# input_amp.net
KiCad netlist of a schematic drawn in EAGLE
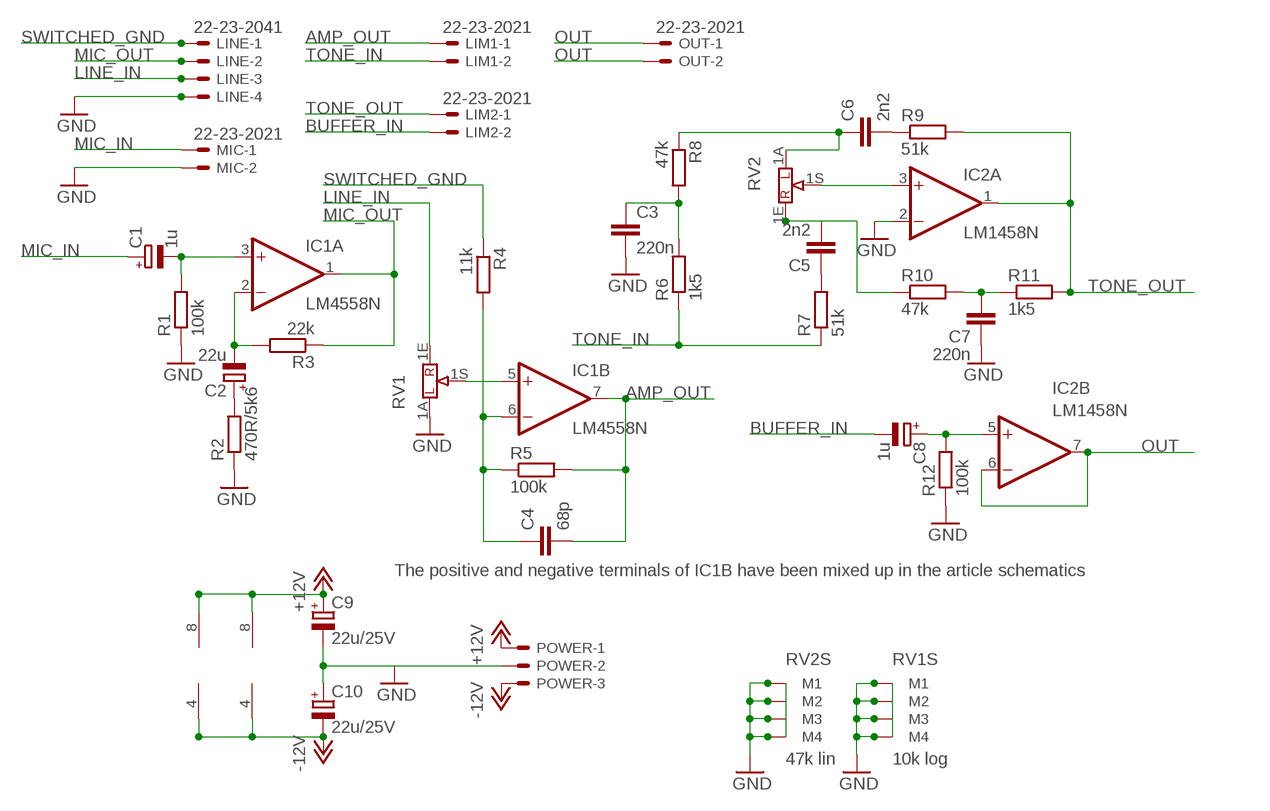
[diagram p0: schematic, sheet 1]

(export (version "E")
  (design (tool "Eeschema 10.0.6"))
  (components
    (comp (ref "C1")
      (value "1u")
      (footprint "eagle-import:E2,5-5")
      (libsource (lib "eagle-import") (part "CPOL-EUE2.5-5"))
    )
    (comp (ref "C2")
      (value "22u")
      (footprint "eagle-import:E2,5-5")
      (libsource (lib "eagle-import") (part "CPOL-EUE2.5-5"))
    )
    (comp (ref "C3")
      (value "220n")
      (footprint "eagle-import:C050-025X075")
      (libsource (lib "eagle-import") (part "C-EU050-025X075"))
    )
    (comp (ref "C4")
      (value "68p")
      (footprint "eagle-import:C025-025X050")
      (libsource (lib "eagle-import") (part "C-EU025-025X050"))
    )
    (comp (ref "C5")
      (value "2n2")
      (footprint "eagle-import:C050-025X075")
      (libsource (lib "eagle-import") (part "C-EU050-025X075"))
    )
    (comp (ref "C6")
      (value "2n2")
      (footprint "eagle-import:C050-025X075")
      (libsource (lib "eagle-import") (part "C-EU050-025X075"))
    )
    (comp (ref "C7")
      (value "220n")
      (footprint "eagle-import:C050-025X075")
      (libsource (lib "eagle-import") (part "C-EU050-025X075"))
    )
    (comp (ref "C8")
      (value "1u")
      (footprint "eagle-import:E2,5-5")
      (libsource (lib "eagle-import") (part "CPOL-EUE2.5-5"))
    )
    (comp (ref "C9")
      (value "22u/25V")
      (footprint "eagle-import:E2,5-5")
      (libsource (lib "eagle-import") (part "CPOL-EUE2.5-5"))
    )
    (comp (ref "C10")
      (value "22u/25V")
      (footprint "eagle-import:E2,5-5")
      (libsource (lib "eagle-import") (part "CPOL-EUE2.5-5"))
    )
    (comp (ref "IC1")
      (value "LM4558N")
      (footprint "eagle-import:DIL08")
      (libsource (lib "eagle-import") (part "4558NLM"))
    )
    (comp (ref "IC2")
      (value "LM1458N")
      (footprint "eagle-import:DIL08")
      (libsource (lib "eagle-import") (part "1458NLM"))
    )
    (comp (ref "LIM1")
      (value "22-23-2021")
      (footprint "eagle-import:22-23-2021")
      (fields (field (name "MF") "MOLEX"))
      (libsource (lib "eagle-import") (part "22-23-2021"))
    )
    (comp (ref "LIM2")
      (value "22-23-2021")
      (footprint "eagle-import:22-23-2021")
      (fields (field (name "MF") "MOLEX"))
      (libsource (lib "eagle-import") (part "22-23-2021"))
    )
    (comp (ref "LINE")
      (value "22-23-2041")
      (footprint "eagle-import:22-23-2041")
      (fields (field (name "MF") "MOLEX"))
      (libsource (lib "eagle-import") (part "22-23-2041"))
    )
    (comp (ref "MIC")
      (value "22-23-2021")
      (footprint "eagle-import:22-23-2021")
      (fields (field (name "MF") "MOLEX"))
      (libsource (lib "eagle-import") (part "22-23-2021"))
    )
    (comp (ref "OUT")
      (value "22-23-2021")
      (footprint "eagle-import:22-23-2021")
      (fields (field (name "MF") "MOLEX"))
      (libsource (lib "eagle-import") (part "22-23-2021"))
    )
    (comp (ref "POWER")
      (value "KK-156-3")
      (footprint "eagle-import:KK-156-3")
      (libsource (lib "eagle-import") (part "KK-156-3"))
    )
    (comp (ref "R1")
      (value "100k")
      (footprint "eagle-import:0207_7")
      (libsource (lib "eagle-import") (part "R-EU_0207/7"))
    )
    (comp (ref "R2")
      (value "470R/5k6")
      (footprint "eagle-import:0207_7")
      (libsource (lib "eagle-import") (part "R-EU_0207/7"))
    )
    (comp (ref "R3")
      (value "22k")
      (footprint "eagle-import:0207_7")
      (libsource (lib "eagle-import") (part "R-EU_0207/7"))
    )
    (comp (ref "R4")
      (value "11k")
      (footprint "eagle-import:0207_7")
      (libsource (lib "eagle-import") (part "R-EU_0207/7"))
    )
    (comp (ref "R5")
      (value "100k")
      (footprint "eagle-import:0207_7")
      (libsource (lib "eagle-import") (part "R-EU_0207/7"))
    )
    (comp (ref "R6")
      (value "1k5")
      (footprint "eagle-import:0207_7")
      (libsource (lib "eagle-import") (part "R-EU_0207/7"))
    )
    (comp (ref "R7")
      (value "51k")
      (footprint "eagle-import:0207_7")
      (libsource (lib "eagle-import") (part "R-EU_0207/7"))
    )
    (comp (ref "R8")
      (value "47k")
      (footprint "eagle-import:0207_7")
      (libsource (lib "eagle-import") (part "R-EU_0207/7"))
    )
    (comp (ref "R9")
      (value "51k")
      (footprint "eagle-import:0207_7")
      (libsource (lib "eagle-import") (part "R-EU_0207/7"))
    )
    (comp (ref "R10")
      (value "47k")
      (footprint "eagle-import:0207_7")
      (libsource (lib "eagle-import") (part "R-EU_0207/7"))
    )
    (comp (ref "R11")
      (value "1k5")
      (footprint "eagle-import:0207_7")
      (libsource (lib "eagle-import") (part "R-EU_0207/7"))
    )
    (comp (ref "R12")
      (value "100k")
      (footprint "eagle-import:0207_7")
      (libsource (lib "eagle-import") (part "R-EU_0207/7"))
    )
    (comp (ref "RV1")
      (value "10k log")
      (footprint "eagle-import:POT16_W_BRACKET")
      (libsource (lib "eagle-import") (part "POT16_W_BRACKET{dblquote}{dblquote}"))
    )
    (comp (ref "RV2")
      (value "47k lin")
      (footprint "eagle-import:POT16_W_BRACKET")
      (libsource (lib "eagle-import") (part "POT16_W_BRACKET{dblquote}{dblquote}"))
    )
  )
  (nets
    (net (code "1") (name "+12V") (class "Default")
      (node (ref "C9") (pin "+") (pinfunction "+_+") (pintype "passive"))
      (node (ref "IC1") (pin "8") (pinfunction "V+_8") (pintype "power_in"))
      (node (ref "IC2") (pin "8") (pinfunction "V+_8") (pintype "power_in"))
      (node (ref "POWER") (pin "1") (pinfunction "S_1") (pintype "passive"))
    )
    (net (code "2") (name "-12V") (class "Default")
      (node (ref "C10") (pin "-") (pinfunction "-_-") (pintype "passive"))
      (node (ref "IC1") (pin "4") (pinfunction "V-_4") (pintype "power_in"))
      (node (ref "IC2") (pin "4") (pinfunction "V-_4") (pintype "power_in"))
      (node (ref "POWER") (pin "3") (pinfunction "S_3") (pintype "passive"))
    )
    (net (code "3") (name "/AMP_OUT") (class "Default")
      (node (ref "C4") (pin "2") (pinfunction "2_2") (pintype "passive"))
      (node (ref "IC1") (pin "7") (pinfunction "OUT_7") (pintype "output"))
      (node (ref "LIM1") (pin "1") (pinfunction "S_1") (pintype "passive"))
      (node (ref "R5") (pin "2") (pinfunction "2_2") (pintype "passive"))
    )
    (net (code "4") (name "/BUFFER_IN") (class "Default")
      (node (ref "C8") (pin "-") (pinfunction "-_-") (pintype "passive"))
      (node (ref "LIM2") (pin "2") (pinfunction "S_2") (pintype "passive"))
    )
    (net (code "5") (name "/LINE_IN") (class "Default")
      (node (ref "LINE") (pin "3") (pinfunction "S_3") (pintype "passive"))
      (node (ref "RV1") (pin "1E") (pinfunction "1E_1E") (pintype "passive"))
    )
    (net (code "6") (name "/MIC_IN") (class "Default")
      (node (ref "C1") (pin "+") (pinfunction "+_+") (pintype "passive"))
      (node (ref "MIC") (pin "1") (pinfunction "S_1") (pintype "passive"))
    )
    (net (code "7") (name "/MIC_OUT") (class "Default")
      (node (ref "IC1") (pin "1") (pinfunction "OUT_1") (pintype "output"))
      (node (ref "LINE") (pin "2") (pinfunction "S_2") (pintype "passive"))
      (node (ref "R3") (pin "1") (pinfunction "1_1") (pintype "passive"))
    )
    (net (code "8") (name "/OUT") (class "Default")
      (node (ref "IC2") (pin "6") (pinfunction "-IN_6") (pintype "input"))
      (node (ref "IC2") (pin "7") (pinfunction "OUT_7") (pintype "output"))
      (node (ref "OUT") (pin "1") (pinfunction "S_1") (pintype "passive"))
      (node (ref "OUT") (pin "2") (pinfunction "S_2") (pintype "passive"))
    )
    (net (code "9") (name "/SWITCHED_GND") (class "Default")
      (node (ref "LINE") (pin "1") (pinfunction "S_1") (pintype "passive"))
      (node (ref "R4") (pin "1") (pinfunction "1_1") (pintype "passive"))
    )
    (net (code "10") (name "/TONE_IN") (class "Default")
      (node (ref "LIM1") (pin "2") (pinfunction "S_2") (pintype "passive"))
      (node (ref "R6") (pin "1") (pinfunction "1_1") (pintype "passive"))
      (node (ref "R7") (pin "1") (pinfunction "1_1") (pintype "passive"))
    )
    (net (code "11") (name "/TONE_OUT") (class "Default")
      (node (ref "IC2") (pin "1") (pinfunction "OUT_1") (pintype "output"))
      (node (ref "LIM2") (pin "1") (pinfunction "S_1") (pintype "passive"))
      (node (ref "R11") (pin "2") (pinfunction "2_2") (pintype "passive"))
      (node (ref "R9") (pin "2") (pinfunction "2_2") (pintype "passive"))
    )
    (net (code "12") (name "GND") (class "Default")
      (node (ref "C10") (pin "+") (pinfunction "+_+") (pintype "passive"))
      (node (ref "C3") (pin "2") (pinfunction "2_2") (pintype "passive"))
      (node (ref "C7") (pin "1") (pinfunction "1_1") (pintype "passive"))
      (node (ref "C9") (pin "-") (pinfunction "-_-") (pintype "passive"))
      (node (ref "IC2") (pin "2") (pinfunction "-IN_2") (pintype "input"))
      (node (ref "LINE") (pin "4") (pinfunction "S_4") (pintype "passive"))
      (node (ref "MIC") (pin "2") (pinfunction "S_2") (pintype "passive"))
      (node (ref "POWER") (pin "2") (pinfunction "S_2") (pintype "passive"))
      (node (ref "R1") (pin "1") (pinfunction "1_1") (pintype "passive"))
      (node (ref "R12") (pin "1") (pinfunction "1_1") (pintype "passive"))
      (node (ref "R2") (pin "1") (pinfunction "1_1") (pintype "passive"))
      (node (ref "RV1") (pin "1A") (pinfunction "1A_1A") (pintype "passive"))
      (node (ref "RV1") (pin "M1") (pinfunction "M1_M1") (pintype "passive"))
      (node (ref "RV1") (pin "M2") (pinfunction "M2_M2") (pintype "passive"))
      (node (ref "RV1") (pin "M3") (pinfunction "M3_M3") (pintype "passive"))
      (node (ref "RV1") (pin "M4") (pinfunction "M4_M4") (pintype "passive"))
      (node (ref "RV2") (pin "M1") (pinfunction "M1_M1") (pintype "passive"))
      (node (ref "RV2") (pin "M2") (pinfunction "M2_M2") (pintype "passive"))
      (node (ref "RV2") (pin "M3") (pinfunction "M3_M3") (pintype "passive"))
      (node (ref "RV2") (pin "M4") (pinfunction "M4_M4") (pintype "passive"))
    )
    (net (code "13") (name "Net-(C2-Pad+)") (class "Default")
      (node (ref "C2") (pin "+") (pinfunction "+_+") (pintype "passive"))
      (node (ref "R2") (pin "2") (pinfunction "2_2") (pintype "passive"))
    )
    (net (code "14") (name "Net-(C3-Pad1)") (class "Default")
      (node (ref "C3") (pin "1") (pinfunction "1_1") (pintype "passive"))
      (node (ref "R6") (pin "2") (pinfunction "2_2") (pintype "passive"))
      (node (ref "R8") (pin "2") (pinfunction "2_2") (pintype "passive"))
    )
    (net (code "15") (name "Net-(C5-Pad1)") (class "Default")
      (node (ref "C5") (pin "1") (pinfunction "1_1") (pintype "passive"))
      (node (ref "R7") (pin "2") (pinfunction "2_2") (pintype "passive"))
    )
    (net (code "16") (name "Net-(C5-Pad2)") (class "Default")
      (node (ref "C5") (pin "2") (pinfunction "2_2") (pintype "passive"))
      (node (ref "R10") (pin "1") (pinfunction "1_1") (pintype "passive"))
      (node (ref "RV2") (pin "1E") (pinfunction "1E_1E") (pintype "passive"))
    )
    (net (code "17") (name "Net-(C6-Pad1)") (class "Default")
      (node (ref "C6") (pin "1") (pinfunction "1_1") (pintype "passive"))
      (node (ref "R8") (pin "1") (pinfunction "1_1") (pintype "passive"))
      (node (ref "RV2") (pin "1A") (pinfunction "1A_1A") (pintype "passive"))
    )
    (net (code "18") (name "Net-(C6-Pad2)") (class "Default")
      (node (ref "C6") (pin "2") (pinfunction "2_2") (pintype "passive"))
      (node (ref "R9") (pin "1") (pinfunction "1_1") (pintype "passive"))
    )
    (net (code "19") (name "Net-(C7-Pad2)") (class "Default")
      (node (ref "C7") (pin "2") (pinfunction "2_2") (pintype "passive"))
      (node (ref "R10") (pin "2") (pinfunction "2_2") (pintype "passive"))
      (node (ref "R11") (pin "1") (pinfunction "1_1") (pintype "passive"))
    )
    (net (code "20") (name "Net-(IC1A-+IN)") (class "Default")
      (node (ref "C1") (pin "-") (pinfunction "-_-") (pintype "passive"))
      (node (ref "IC1") (pin "3") (pinfunction "+IN_3") (pintype "input"))
      (node (ref "R1") (pin "2") (pinfunction "2_2") (pintype "passive"))
    )
    (net (code "21") (name "Net-(IC1A--IN)") (class "Default")
      (node (ref "C2") (pin "-") (pinfunction "-_-") (pintype "passive"))
      (node (ref "IC1") (pin "2") (pinfunction "-IN_2") (pintype "input"))
      (node (ref "R3") (pin "2") (pinfunction "2_2") (pintype "passive"))
    )
    (net (code "22") (name "Net-(IC1B-+IN)") (class "Default")
      (node (ref "IC1") (pin "5") (pinfunction "+IN_5") (pintype "input"))
      (node (ref "RV1") (pin "1S") (pinfunction "1S_1S") (pintype "passive"))
    )
    (net (code "23") (name "Net-(IC1B--IN)") (class "Default")
      (node (ref "C4") (pin "1") (pinfunction "1_1") (pintype "passive"))
      (node (ref "IC1") (pin "6") (pinfunction "-IN_6") (pintype "input"))
      (node (ref "R4") (pin "2") (pinfunction "2_2") (pintype "passive"))
      (node (ref "R5") (pin "1") (pinfunction "1_1") (pintype "passive"))
    )
    (net (code "24") (name "Net-(IC2A-+IN)") (class "Default")
      (node (ref "IC2") (pin "3") (pinfunction "+IN_3") (pintype "input"))
      (node (ref "RV2") (pin "1S") (pinfunction "1S_1S") (pintype "passive"))
    )
    (net (code "25") (name "Net-(IC2B-+IN)") (class "Default")
      (node (ref "C8") (pin "+") (pinfunction "+_+") (pintype "passive"))
      (node (ref "IC2") (pin "5") (pinfunction "+IN_5") (pintype "input"))
      (node (ref "R12") (pin "2") (pinfunction "2_2") (pintype "passive"))
    )
  )
)
